# 06-5V_To_3V3.net
KiCad netlist of a schematic drawn in Altium Designer
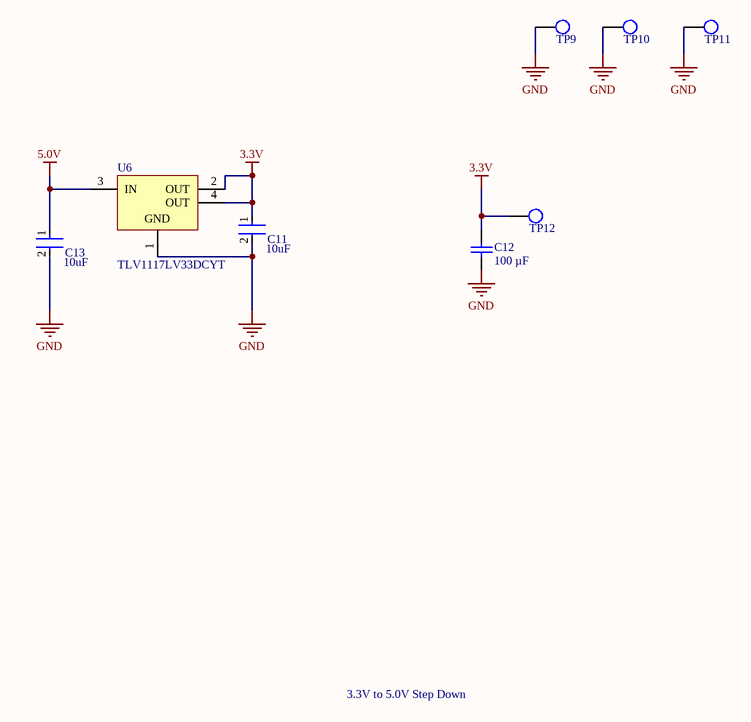
[diagram p0: 06-5V_To_3V3.SchDoc]

(export (version "E")
  (design (tool "Eeschema 10.0.6"))
  (components
    (comp (ref "C11")
      (value "CL21A106KQCLNNC")
      (footprint "FP-CL21-IPC_B")
      (description "CL21 Series 0805 10uF 6.3V ±10% Tolerance X5R Multilayer Ceramic Chip Capacitor")
      (fields (field (name "CAPACITANCE") "10uF") (field (name "TOLERANCE") "10%"))
      (libsource (lib "Altium Content Vault") (part "b4654b650e69147ec39a6b967a45e02"))
    )
    (comp (ref "C12")
      (value "EEEHA1A101WP")
      (footprint "CAP_EEEHA1A101WP:CAP_EEEHA1A101WP")
      (description "100ÂµF 10V Aluminum Electrolytic Capacitors Radial, Can - SMD 1000 Hrs @ 105Â°C")
      (fields
        (field (name "MF") "Panasonic")
        (field (name "MP") "EEE-HA1A101WP")
        (field (name "CAPACITANCE") "100 µF")
      )
      (libsource (lib "team6") (part "EEEHA1A101WP"))
    )
    (comp (ref "C13")
      (value "CL21A106KQCLNNC")
      (footprint "FP-CL21-IPC_B")
      (description "CL21 Series 0805 10uF 6.3V ±10% Tolerance X5R Multilayer Ceramic Chip Capacitor")
      (fields (field (name "CAPACITANCE") "10uF") (field (name "TOLERANCE") "10%"))
      (libsource (lib "Altium Content Vault") (part "b4654b650e69147ec39a6b967a45e02"))
    )
    (comp (ref "TP9")
      (value "TP_1206")
      (footprint "TP-SMC-1206")
      (description "Test Point SMD 1206")
      (fields
        (field (name "MANUFACTURER") "TE Connectivity (Tyco Electronics)")
        (field (name "MANUFACTURER PART NUMBER") "1625854-1")
      )
      (libsource (lib "ECE453-F22-Power") (part "TP_1206"))
    )
    (comp (ref "TP10")
      (value "TP_1206")
      (footprint "TP-SMC-1206")
      (description "Test Point SMD 1206")
      (fields
        (field (name "MANUFACTURER") "TE Connectivity (Tyco Electronics)")
        (field (name "MANUFACTURER PART NUMBER") "1625854-1")
      )
      (libsource (lib "ECE453-F22-Power") (part "TP_1206"))
    )
    (comp (ref "TP11")
      (value "TP_1206")
      (footprint "TP-SMC-1206")
      (description "Test Point SMD 1206")
      (fields
        (field (name "MANUFACTURER") "TE Connectivity (Tyco Electronics)")
        (field (name "MANUFACTURER PART NUMBER") "1625854-1")
      )
      (libsource (lib "ECE453-F22-Power") (part "TP_1206"))
    )
    (comp (ref "TP12")
      (value "TP_1206")
      (footprint "TP-SMC-1206")
      (description "Test Point SMD 1206")
      (fields
        (field (name "MANUFACTURER") "TE Connectivity (Tyco Electronics)")
        (field (name "MANUFACTURER PART NUMBER") "1625854-1")
      )
      (libsource (lib "ECE453-F22-Power") (part "TP_1206"))
    )
    (comp (ref "U6")
      (value "TLV1117LV33DCYT")
      (footprint "DCY0004A_M")
      (fields (field (name "MANUFACTURER") "Texas Instruments"))
      (libsource (lib "Altium Content Vault") (part "TI-TLV1117LV33DCY4"))
    )
  )
  (nets
    (net (code "1") (name "3.3V") (class "Default")
      (node (ref "C11") (pin "1") (pinfunction "1_1") (pintype "passive"))
      (node (ref "C12") (pin "2") (pinfunction "2_2") (pintype "passive"))
      (node (ref "TP12") (pin "1") (pintype "passive"))
      (node (ref "U6") (pin "2") (pinfunction "OUT_2") (pintype "power_in"))
      (node (ref "U6") (pin "4") (pinfunction "OUT_4") (pintype "power_in"))
    )
    (net (code "2") (name "5.0V") (class "Default")
      (node (ref "C13") (pin "1") (pinfunction "1_1") (pintype "passive"))
      (node (ref "U6") (pin "3") (pinfunction "IN_3") (pintype "power_in"))
    )
    (net (code "3") (name "GND") (class "Default")
      (node (ref "C11") (pin "2") (pinfunction "2_2") (pintype "passive"))
      (node (ref "C12") (pin "1") (pinfunction "1_1") (pintype "passive"))
      (node (ref "C13") (pin "2") (pinfunction "2_2") (pintype "passive"))
      (node (ref "TP10") (pin "1") (pintype "passive"))
      (node (ref "TP11") (pin "1") (pintype "passive"))
      (node (ref "TP9") (pin "1") (pintype "passive"))
      (node (ref "U6") (pin "1") (pinfunction "GND_1") (pintype "power_in"))
    )
  )
)
